# old_control_board.net
KiCad netlist of a schematic drawn in EAGLE
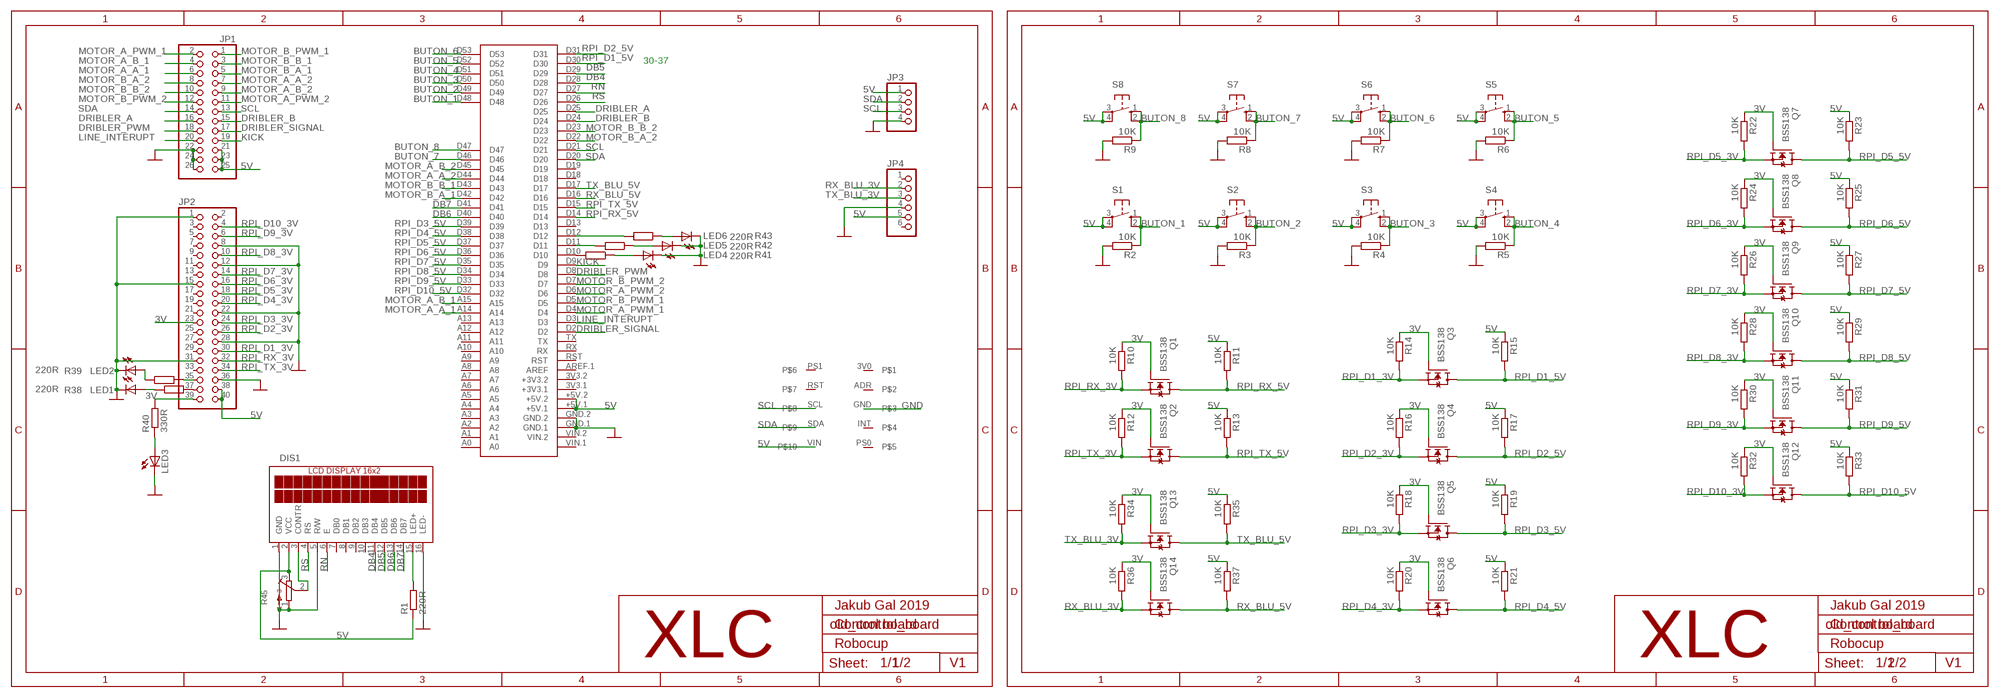
[diagram p0: schematic, sheet 1]

(export (version "E")
  (design (tool "Eeschema 10.0.6"))
  (components
    (comp (ref "DIS1")
      (value "LCD_DISPLEJ_16X2Z")
      (footprint "eagle-import:LCD_DISPLEJ_16X2")
      (libsource (lib "eagle-import") (part "LCD_DISPLEJ_16X2Z"))
    )
    (comp (ref "JP1")
      (value "PINHD-2X13_2.54")
      (footprint "eagle-import:2X13")
      (libsource (lib "eagle-import") (part "PINHD-2X13_2.54"))
    )
    (comp (ref "JP2")
      (value "PINHD-2X20_2.54")
      (footprint "eagle-import:2X20")
      (libsource (lib "eagle-import") (part "PINHD-2X20_2.54"))
    )
    (comp (ref "JP3")
      (value "PINHD-1X4_2.54")
      (footprint "eagle-import:1X04")
      (libsource (lib "eagle-import") (part "PINHD-1X4_2.54"))
    )
    (comp (ref "JP4")
      (value "PINHD-1X6_2.54")
      (footprint "eagle-import:1X06")
      (libsource (lib "eagle-import") (part "PINHD-1X6_2.54"))
    )
    (comp (ref "LED1")
      (value "LEDCHIPLED_0603")
      (footprint "eagle-import:CHIPLED_0603")
      (libsource (lib "eagle-import") (part "LEDCHIPLED_0603"))
    )
    (comp (ref "LED2")
      (value "LEDCHIPLED_0603")
      (footprint "eagle-import:CHIPLED_0603")
      (libsource (lib "eagle-import") (part "LEDCHIPLED_0603"))
    )
    (comp (ref "LED3")
      (value "LEDCHIPLED_0603")
      (footprint "eagle-import:CHIPLED_0603")
      (libsource (lib "eagle-import") (part "LEDCHIPLED_0603"))
    )
    (comp (ref "LED4")
      (value "LEDCHIPLED_0603")
      (footprint "eagle-import:CHIPLED_0603")
      (libsource (lib "eagle-import") (part "LEDCHIPLED_0603"))
    )
    (comp (ref "LED5")
      (value "LEDCHIPLED_0603")
      (footprint "eagle-import:CHIPLED_0603")
      (libsource (lib "eagle-import") (part "LEDCHIPLED_0603"))
    )
    (comp (ref "LED6")
      (value "LEDCHIPLED_0603")
      (footprint "eagle-import:CHIPLED_0603")
      (libsource (lib "eagle-import") (part "LEDCHIPLED_0603"))
    )
    (comp (ref "Q1")
      (value "BSS138")
      (footprint "eagle-import:SOT23")
      (fields (field (name "MF") "Fairchild"))
      (libsource (lib "eagle-import") (part "BSS138"))
    )
    (comp (ref "Q2")
      (value "BSS138")
      (footprint "eagle-import:SOT23")
      (fields (field (name "MF") "Fairchild"))
      (libsource (lib "eagle-import") (part "BSS138"))
    )
    (comp (ref "Q3")
      (value "BSS138")
      (footprint "eagle-import:SOT23")
      (fields (field (name "MF") "Fairchild"))
      (libsource (lib "eagle-import") (part "BSS138"))
    )
    (comp (ref "Q4")
      (value "BSS138")
      (footprint "eagle-import:SOT23")
      (fields (field (name "MF") "Fairchild"))
      (libsource (lib "eagle-import") (part "BSS138"))
    )
    (comp (ref "Q5")
      (value "BSS138")
      (footprint "eagle-import:SOT23")
      (fields (field (name "MF") "Fairchild"))
      (libsource (lib "eagle-import") (part "BSS138"))
    )
    (comp (ref "Q6")
      (value "BSS138")
      (footprint "eagle-import:SOT23")
      (fields (field (name "MF") "Fairchild"))
      (libsource (lib "eagle-import") (part "BSS138"))
    )
    (comp (ref "Q7")
      (value "BSS138")
      (footprint "eagle-import:SOT23")
      (fields (field (name "MF") "Fairchild"))
      (libsource (lib "eagle-import") (part "BSS138"))
    )
    (comp (ref "Q8")
      (value "BSS138")
      (footprint "eagle-import:SOT23")
      (fields (field (name "MF") "Fairchild"))
      (libsource (lib "eagle-import") (part "BSS138"))
    )
    (comp (ref "Q9")
      (value "BSS138")
      (footprint "eagle-import:SOT23")
      (fields (field (name "MF") "Fairchild"))
      (libsource (lib "eagle-import") (part "BSS138"))
    )
    (comp (ref "Q10")
      (value "BSS138")
      (footprint "eagle-import:SOT23")
      (fields (field (name "MF") "Fairchild"))
      (libsource (lib "eagle-import") (part "BSS138"))
    )
    (comp (ref "Q11")
      (value "BSS138")
      (footprint "eagle-import:SOT23")
      (fields (field (name "MF") "Fairchild"))
      (libsource (lib "eagle-import") (part "BSS138"))
    )
    (comp (ref "Q12")
      (value "BSS138")
      (footprint "eagle-import:SOT23")
      (fields (field (name "MF") "Fairchild"))
      (libsource (lib "eagle-import") (part "BSS138"))
    )
    (comp (ref "Q13")
      (value "BSS138")
      (footprint "eagle-import:SOT23")
      (fields (field (name "MF") "Fairchild"))
      (libsource (lib "eagle-import") (part "BSS138"))
    )
    (comp (ref "Q14")
      (value "BSS138")
      (footprint "eagle-import:SOT23")
      (fields (field (name "MF") "Fairchild"))
      (libsource (lib "eagle-import") (part "BSS138"))
    )
    (comp (ref "R1")
      (value "220R")
      (footprint "eagle-import:R0603")
      (libsource (lib "eagle-import") (part "R-EU_R0603"))
    )
    (comp (ref "R2")
      (value "10K")
      (footprint "eagle-import:R0603")
      (libsource (lib "eagle-import") (part "R-EU_R0603"))
    )
    (comp (ref "R3")
      (value "10K")
      (footprint "eagle-import:R0603")
      (libsource (lib "eagle-import") (part "R-EU_R0603"))
    )
    (comp (ref "R4")
      (value "10K")
      (footprint "eagle-import:R0603")
      (libsource (lib "eagle-import") (part "R-EU_R0603"))
    )
    (comp (ref "R5")
      (value "10K")
      (footprint "eagle-import:R0603")
      (libsource (lib "eagle-import") (part "R-EU_R0603"))
    )
    (comp (ref "R6")
      (value "10K")
      (footprint "eagle-import:R0603")
      (libsource (lib "eagle-import") (part "R-EU_R0603"))
    )
    (comp (ref "R7")
      (value "10K")
      (footprint "eagle-import:R0603")
      (libsource (lib "eagle-import") (part "R-EU_R0603"))
    )
    (comp (ref "R8")
      (value "10K")
      (footprint "eagle-import:R0603")
      (libsource (lib "eagle-import") (part "R-EU_R0603"))
    )
    (comp (ref "R9")
      (value "10K")
      (footprint "eagle-import:R0603")
      (libsource (lib "eagle-import") (part "R-EU_R0603"))
    )
    (comp (ref "R10")
      (value "10K")
      (footprint "eagle-import:R0603")
      (libsource (lib "eagle-import") (part "R-EU_R0603"))
    )
    (comp (ref "R11")
      (value "10K")
      (footprint "eagle-import:R0603")
      (libsource (lib "eagle-import") (part "R-EU_R0603"))
    )
    (comp (ref "R12")
      (value "10K")
      (footprint "eagle-import:R0603")
      (libsource (lib "eagle-import") (part "R-EU_R0603"))
    )
    (comp (ref "R13")
      (value "10K")
      (footprint "eagle-import:R0603")
      (libsource (lib "eagle-import") (part "R-EU_R0603"))
    )
    (comp (ref "R14")
      (value "10K")
      (footprint "eagle-import:R0603")
      (libsource (lib "eagle-import") (part "R-EU_R0603"))
    )
    (comp (ref "R15")
      (value "10K")
      (footprint "eagle-import:R0603")
      (libsource (lib "eagle-import") (part "R-EU_R0603"))
    )
    (comp (ref "R16")
      (value "10K")
      (footprint "eagle-import:R0603")
      (libsource (lib "eagle-import") (part "R-EU_R0603"))
    )
    (comp (ref "R17")
      (value "10K")
      (footprint "eagle-import:R0603")
      (libsource (lib "eagle-import") (part "R-EU_R0603"))
    )
    (comp (ref "R18")
      (value "10K")
      (footprint "eagle-import:R0603")
      (libsource (lib "eagle-import") (part "R-EU_R0603"))
    )
    (comp (ref "R19")
      (value "10K")
      (footprint "eagle-import:R0603")
      (libsource (lib "eagle-import") (part "R-EU_R0603"))
    )
    (comp (ref "R20")
      (value "10K")
      (footprint "eagle-import:R0603")
      (libsource (lib "eagle-import") (part "R-EU_R0603"))
    )
    (comp (ref "R21")
      (value "10K")
      (footprint "eagle-import:R0603")
      (libsource (lib "eagle-import") (part "R-EU_R0603"))
    )
    (comp (ref "R22")
      (value "10K")
      (footprint "eagle-import:R0603")
      (libsource (lib "eagle-import") (part "R-EU_R0603"))
    )
    (comp (ref "R23")
      (value "10K")
      (footprint "eagle-import:R0603")
      (libsource (lib "eagle-import") (part "R-EU_R0603"))
    )
    (comp (ref "R24")
      (value "10K")
      (footprint "eagle-import:R0603")
      (libsource (lib "eagle-import") (part "R-EU_R0603"))
    )
    (comp (ref "R25")
      (value "10K")
      (footprint "eagle-import:R0603")
      (libsource (lib "eagle-import") (part "R-EU_R0603"))
    )
    (comp (ref "R26")
      (value "10K")
      (footprint "eagle-import:R0603")
      (libsource (lib "eagle-import") (part "R-EU_R0603"))
    )
    (comp (ref "R27")
      (value "10K")
      (footprint "eagle-import:R0603")
      (libsource (lib "eagle-import") (part "R-EU_R0603"))
    )
    (comp (ref "R28")
      (value "10K")
      (footprint "eagle-import:R0603")
      (libsource (lib "eagle-import") (part "R-EU_R0603"))
    )
    (comp (ref "R29")
      (value "10K")
      (footprint "eagle-import:R0603")
      (libsource (lib "eagle-import") (part "R-EU_R0603"))
    )
    (comp (ref "R30")
      (value "10K")
      (footprint "eagle-import:R0603")
      (libsource (lib "eagle-import") (part "R-EU_R0603"))
    )
    (comp (ref "R31")
      (value "10K")
      (footprint "eagle-import:R0603")
      (libsource (lib "eagle-import") (part "R-EU_R0603"))
    )
    (comp (ref "R32")
      (value "10K")
      (footprint "eagle-import:R0603")
      (libsource (lib "eagle-import") (part "R-EU_R0603"))
    )
    (comp (ref "R33")
      (value "10K")
      (footprint "eagle-import:R0603")
      (libsource (lib "eagle-import") (part "R-EU_R0603"))
    )
    (comp (ref "R34")
      (value "10K")
      (footprint "eagle-import:R0603")
      (libsource (lib "eagle-import") (part "R-EU_R0603"))
    )
    (comp (ref "R35")
      (value "10K")
      (footprint "eagle-import:R0603")
      (libsource (lib "eagle-import") (part "R-EU_R0603"))
    )
    (comp (ref "R36")
      (value "10K")
      (footprint "eagle-import:R0603")
      (libsource (lib "eagle-import") (part "R-EU_R0603"))
    )
    (comp (ref "R37")
      (value "10K")
      (footprint "eagle-import:R0603")
      (libsource (lib "eagle-import") (part "R-EU_R0603"))
    )
    (comp (ref "R38")
      (value "220R")
      (footprint "eagle-import:R0603")
      (libsource (lib "eagle-import") (part "R-EU_R0603"))
    )
    (comp (ref "R39")
      (value "220R")
      (footprint "eagle-import:R0603")
      (libsource (lib "eagle-import") (part "R-EU_R0603"))
    )
    (comp (ref "R40")
      (value "330R")
      (footprint "eagle-import:R0603")
      (libsource (lib "eagle-import") (part "R-EU_R0603"))
    )
    (comp (ref "R41")
      (value "220R")
      (footprint "eagle-import:R0603")
      (libsource (lib "eagle-import") (part "R-EU_R0603"))
    )
    (comp (ref "R42")
      (value "220R")
      (footprint "eagle-import:R0603")
      (libsource (lib "eagle-import") (part "R-EU_R0603"))
    )
    (comp (ref "R43")
      (value "220R")
      (footprint "eagle-import:R0603")
      (libsource (lib "eagle-import") (part "R-EU_R0603"))
    )
    (comp (ref "R45")
      (value "3362P")
      (footprint "eagle-import:3362P")
      (libsource (lib "eagle-import") (part "3362P"))
    )
    (comp (ref "S1")
      (value "10-XX")
      (footprint "eagle-import:B3F-10XX")
      (fields (field (name "MPN") "B3F-1000"))
      (libsource (lib "eagle-import") (part "10-XX"))
    )
    (comp (ref "S2")
      (value "10-XX")
      (footprint "eagle-import:B3F-10XX")
      (fields (field (name "MPN") "B3F-1000"))
      (libsource (lib "eagle-import") (part "10-XX"))
    )
    (comp (ref "S3")
      (value "10-XX")
      (footprint "eagle-import:B3F-10XX")
      (fields (field (name "MPN") "B3F-1000"))
      (libsource (lib "eagle-import") (part "10-XX"))
    )
    (comp (ref "S4")
      (value "10-XX")
      (footprint "eagle-import:B3F-10XX")
      (fields (field (name "MPN") "B3F-1000"))
      (libsource (lib "eagle-import") (part "10-XX"))
    )
    (comp (ref "S5")
      (value "10-XX")
      (footprint "eagle-import:B3F-10XX")
      (fields (field (name "MPN") "B3F-1000"))
      (libsource (lib "eagle-import") (part "10-XX"))
    )
    (comp (ref "S6")
      (value "10-XX")
      (footprint "eagle-import:B3F-10XX")
      (fields (field (name "MPN") "B3F-1000"))
      (libsource (lib "eagle-import") (part "10-XX"))
    )
    (comp (ref "S7")
      (value "10-XX")
      (footprint "eagle-import:B3F-10XX")
      (fields (field (name "MPN") "B3F-1000"))
      (libsource (lib "eagle-import") (part "10-XX"))
    )
    (comp (ref "S8")
      (value "10-XX")
      (footprint "eagle-import:B3F-10XX")
      (fields (field (name "MPN") "B3F-1000"))
      (libsource (lib "eagle-import") (part "10-XX"))
    )
    (comp (ref "U$1")
      (value "MEGA2560_MIKRO")
      (footprint "eagle-import:MEGA2560_MIKRO")
      (libsource (lib "eagle-import") (part "MEGA2560_MIKRO"))
    )
    (comp (ref "U$2")
      (value "BNO055")
      (footprint "eagle-import:BNO005")
      (libsource (lib "eagle-import") (part "BNO055"))
    )
  )
  (nets
    (net (code "1") (name "/3V") (class "Default")
      (node (ref "JP2") (pin "23") (pinfunction "23_23") (pintype "passive"))
      (node (ref "JP2") (pin "39") (pinfunction "39_39") (pintype "passive"))
      (node (ref "Q1") (pin "1") (pinfunction "G_1") (pintype "passive"))
      (node (ref "Q10") (pin "1") (pinfunction "G_1") (pintype "passive"))
      (node (ref "Q11") (pin "1") (pinfunction "G_1") (pintype "passive"))
      (node (ref "Q12") (pin "1") (pinfunction "G_1") (pintype "passive"))
      (node (ref "Q13") (pin "1") (pinfunction "G_1") (pintype "passive"))
      (node (ref "Q14") (pin "1") (pinfunction "G_1") (pintype "passive"))
      (node (ref "Q2") (pin "1") (pinfunction "G_1") (pintype "passive"))
      (node (ref "Q3") (pin "1") (pinfunction "G_1") (pintype "passive"))
      (node (ref "Q4") (pin "1") (pinfunction "G_1") (pintype "passive"))
      (node (ref "Q5") (pin "1") (pinfunction "G_1") (pintype "passive"))
      (node (ref "Q6") (pin "1") (pinfunction "G_1") (pintype "passive"))
      (node (ref "Q7") (pin "1") (pinfunction "G_1") (pintype "passive"))
      (node (ref "Q8") (pin "1") (pinfunction "G_1") (pintype "passive"))
      (node (ref "Q9") (pin "1") (pinfunction "G_1") (pintype "passive"))
      (node (ref "R10") (pin "1") (pinfunction "1_1") (pintype "passive"))
      (node (ref "R12") (pin "1") (pinfunction "1_1") (pintype "passive"))
      (node (ref "R14") (pin "1") (pinfunction "1_1") (pintype "passive"))
      (node (ref "R16") (pin "1") (pinfunction "1_1") (pintype "passive"))
      (node (ref "R18") (pin "1") (pinfunction "1_1") (pintype "passive"))
      (node (ref "R20") (pin "1") (pinfunction "1_1") (pintype "passive"))
      (node (ref "R22") (pin "1") (pinfunction "1_1") (pintype "passive"))
      (node (ref "R24") (pin "1") (pinfunction "1_1") (pintype "passive"))
      (node (ref "R26") (pin "1") (pinfunction "1_1") (pintype "passive"))
      (node (ref "R28") (pin "1") (pinfunction "1_1") (pintype "passive"))
      (node (ref "R30") (pin "1") (pinfunction "1_1") (pintype "passive"))
      (node (ref "R32") (pin "1") (pinfunction "1_1") (pintype "passive"))
      (node (ref "R34") (pin "1") (pinfunction "1_1") (pintype "passive"))
      (node (ref "R36") (pin "1") (pinfunction "1_1") (pintype "passive"))
      (node (ref "R40") (pin "2") (pinfunction "2_2") (pintype "passive"))
    )
    (net (code "2") (name "/5V") (class "Default")
      (node (ref "DIS1") (pin "2") (pinfunction "VCC_2") (pintype "power_in"))
      (node (ref "JP1") (pin "21") (pinfunction "21_21") (pintype "passive"))
      (node (ref "JP1") (pin "23") (pinfunction "23_23") (pintype "passive"))
      (node (ref "JP1") (pin "25") (pinfunction "25_25") (pintype "passive"))
      (node (ref "JP2") (pin "38") (pinfunction "38_38") (pintype "passive"))
      (node (ref "JP2") (pin "40") (pinfunction "40_40") (pintype "passive"))
      (node (ref "JP3") (pin "1") (pinfunction "1_1") (pintype "passive"))
      (node (ref "JP4") (pin "5") (pinfunction "5_5") (pintype "passive"))
      (node (ref "R1") (pin "1") (pinfunction "1_1") (pintype "passive"))
      (node (ref "R11") (pin "1") (pinfunction "1_1") (pintype "passive"))
      (node (ref "R13") (pin "1") (pinfunction "1_1") (pintype "passive"))
      (node (ref "R15") (pin "1") (pinfunction "1_1") (pintype "passive"))
      (node (ref "R17") (pin "1") (pinfunction "1_1") (pintype "passive"))
      (node (ref "R19") (pin "1") (pinfunction "1_1") (pintype "passive"))
      (node (ref "R21") (pin "1") (pinfunction "1_1") (pintype "passive"))
      (node (ref "R23") (pin "1") (pinfunction "1_1") (pintype "passive"))
      (node (ref "R25") (pin "1") (pinfunction "1_1") (pintype "passive"))
      (node (ref "R27") (pin "1") (pinfunction "1_1") (pintype "passive"))
      (node (ref "R29") (pin "1") (pinfunction "1_1") (pintype "passive"))
      (node (ref "R31") (pin "1") (pinfunction "1_1") (pintype "passive"))
      (node (ref "R33") (pin "1") (pinfunction "1_1") (pintype "passive"))
      (node (ref "R35") (pin "1") (pinfunction "1_1") (pintype "passive"))
      (node (ref "R37") (pin "1") (pinfunction "1_1") (pintype "passive"))
      (node (ref "R45") (pin "3") (pinfunction "3_3") (pintype "passive"))
      (node (ref "S1") (pin "3") (pinfunction "P_3") (pintype "passive"))
      (node (ref "S1") (pin "4") (pinfunction "P1_4") (pintype "passive"))
      (node (ref "S2") (pin "3") (pinfunction "P_3") (pintype "passive"))
      (node (ref "S2") (pin "4") (pinfunction "P1_4") (pintype "passive"))
      (node (ref "S3") (pin "3") (pinfunction "P_3") (pintype "passive"))
      (node (ref "S3") (pin "4") (pinfunction "P1_4") (pintype "passive"))
      (node (ref "S4") (pin "3") (pinfunction "P_3") (pintype "passive"))
      (node (ref "S4") (pin "4") (pinfunction "P1_4") (pintype "passive"))
      (node (ref "S5") (pin "3") (pinfunction "P_3") (pintype "passive"))
      (node (ref "S5") (pin "4") (pinfunction "P1_4") (pintype "passive"))
      (node (ref "S6") (pin "3") (pinfunction "P_3") (pintype "passive"))
      (node (ref "S6") (pin "4") (pinfunction "P1_4") (pintype "passive"))
      (node (ref "S7") (pin "3") (pinfunction "P_3") (pintype "passive"))
      (node (ref "S7") (pin "4") (pinfunction "P1_4") (pintype "passive"))
      (node (ref "S8") (pin "3") (pinfunction "P_3") (pintype "passive"))
      (node (ref "S8") (pin "4") (pinfunction "P1_4") (pintype "passive"))
      (node (ref "U$1") (pin "+5V.1") (pinfunction "+5V.1_+5V.1") (pintype "bidirectional"))
      (node (ref "U$1") (pin "+5V.2") (pinfunction "+5V.2_+5V.2") (pintype "bidirectional"))
      (node (ref "U$2") (pin "VIN") (pinfunction "P$10_VIN") (pintype "bidirectional"))
    )
    (net (code "3") (name "/BUTON_1") (class "Default")
      (node (ref "R2") (pin "1") (pinfunction "1_1") (pintype "passive"))
      (node (ref "S1") (pin "1") (pinfunction "S_1") (pintype "passive"))
      (node (ref "S1") (pin "2") (pinfunction "S1_2") (pintype "passive"))
      (node (ref "U$1") (pin "D48") (pinfunction "D48_D48") (pintype "bidirectional"))
    )
    (net (code "4") (name "/BUTON_2") (class "Default")
      (node (ref "R3") (pin "1") (pinfunction "1_1") (pintype "passive"))
      (node (ref "S2") (pin "1") (pinfunction "S_1") (pintype "passive"))
      (node (ref "S2") (pin "2") (pinfunction "S1_2") (pintype "passive"))
      (node (ref "U$1") (pin "D49") (pinfunction "D49_D49") (pintype "bidirectional"))
    )
    (net (code "5") (name "/BUTON_3") (class "Default")
      (node (ref "R4") (pin "1") (pinfunction "1_1") (pintype "passive"))
      (node (ref "S3") (pin "1") (pinfunction "S_1") (pintype "passive"))
      (node (ref "S3") (pin "2") (pinfunction "S1_2") (pintype "passive"))
      (node (ref "U$1") (pin "D50") (pinfunction "D50_D50") (pintype "bidirectional"))
    )
    (net (code "6") (name "/BUTON_4") (class "Default")
      (node (ref "R5") (pin "1") (pinfunction "1_1") (pintype "passive"))
      (node (ref "S4") (pin "1") (pinfunction "S_1") (pintype "passive"))
      (node (ref "S4") (pin "2") (pinfunction "S1_2") (pintype "passive"))
      (node (ref "U$1") (pin "D51") (pinfunction "D51_D51") (pintype "bidirectional"))
    )
    (net (code "7") (name "/BUTON_5") (class "Default")
      (node (ref "R6") (pin "1") (pinfunction "1_1") (pintype "passive"))
      (node (ref "S5") (pin "1") (pinfunction "S_1") (pintype "passive"))
      (node (ref "S5") (pin "2") (pinfunction "S1_2") (pintype "passive"))
      (node (ref "U$1") (pin "D52") (pinfunction "D52_D52") (pintype "bidirectional"))
    )
    (net (code "8") (name "/BUTON_6") (class "Default")
      (node (ref "R7") (pin "1") (pinfunction "1_1") (pintype "passive"))
      (node (ref "S6") (pin "1") (pinfunction "S_1") (pintype "passive"))
      (node (ref "S6") (pin "2") (pinfunction "S1_2") (pintype "passive"))
      (node (ref "U$1") (pin "D53") (pinfunction "D53_D53") (pintype "bidirectional"))
    )
    (net (code "9") (name "/BUTON_7") (class "Default")
      (node (ref "R8") (pin "1") (pinfunction "1_1") (pintype "passive"))
      (node (ref "S7") (pin "1") (pinfunction "S_1") (pintype "passive"))
      (node (ref "S7") (pin "2") (pinfunction "S1_2") (pintype "passive"))
      (node (ref "U$1") (pin "D46") (pinfunction "D46_D46") (pintype "bidirectional"))
    )
    (net (code "10") (name "/BUTON_8") (class "Default")
      (node (ref "R9") (pin "1") (pinfunction "1_1") (pintype "passive"))
      (node (ref "S8") (pin "1") (pinfunction "S_1") (pintype "passive"))
      (node (ref "S8") (pin "2") (pinfunction "S1_2") (pintype "passive"))
      (node (ref "U$1") (pin "D47") (pinfunction "D47_D47") (pintype "bidirectional"))
    )
    (net (code "11") (name "/DB4") (class "Default")
      (node (ref "DIS1") (pin "11") (pinfunction "DB4_11") (pintype "bidirectional"))
      (node (ref "U$1") (pin "D28") (pinfunction "D28_D28") (pintype "bidirectional"))
    )
    (net (code "12") (name "/DB5") (class "Default")
      (node (ref "DIS1") (pin "12") (pinfunction "DB5_12") (pintype "bidirectional"))
      (node (ref "U$1") (pin "D29") (pinfunction "D29_D29") (pintype "bidirectional"))
    )
    (net (code "13") (name "/DB6") (class "Default")
      (node (ref "DIS1") (pin "13") (pinfunction "DB6_13") (pintype "bidirectional"))
      (node (ref "U$1") (pin "D40") (pinfunction "D40_D40") (pintype "bidirectional"))
    )
    (net (code "14") (name "/DB7") (class "Default")
      (node (ref "DIS1") (pin "14") (pinfunction "DB7_14") (pintype "bidirectional"))
      (node (ref "U$1") (pin "D41") (pinfunction "D41_D41") (pintype "bidirectional"))
    )
    (net (code "15") (name "/DRIBLER_A") (class "Default")
      (node (ref "JP1") (pin "16") (pinfunction "16_16") (pintype "passive"))
      (node (ref "U$1") (pin "D25") (pinfunction "D25_D25") (pintype "bidirectional"))
    )
    (net (code "16") (name "/DRIBLER_B") (class "Default")
      (node (ref "JP1") (pin "15") (pinfunction "15_15") (pintype "passive"))
      (node (ref "U$1") (pin "D24") (pinfunction "D24_D24") (pintype "bidirectional"))
    )
    (net (code "17") (name "/DRIBLER_PWM") (class "Default")
      (node (ref "JP1") (pin "18") (pinfunction "18_18") (pintype "passive"))
      (node (ref "U$1") (pin "D8") (pinfunction "D8_D8") (pintype "bidirectional"))
    )
    (net (code "18") (name "/DRIBLER_SIGNAL") (class "Default")
      (node (ref "JP1") (pin "17") (pinfunction "17_17") (pintype "passive"))
      (node (ref "U$1") (pin "D2") (pinfunction "D2_D2") (pintype "bidirectional"))
    )
    (net (code "19") (name "/KICK") (class "Default")
      (node (ref "JP1") (pin "19") (pinfunction "19_19") (pintype "passive"))
      (node (ref "U$1") (pin "D9") (pinfunction "D9_D9") (pintype "bidirectional"))
    )
    (net (code "20") (name "/LINE_INTERUPT") (class "Default")
      (node (ref "JP1") (pin "20") (pinfunction "20_20") (pintype "passive"))
      (node (ref "U$1") (pin "D3") (pinfunction "D3_D3") (pintype "bidirectional"))
    )
    (net (code "21") (name "/MOTOR_A_A_1") (class "Default")
      (node (ref "JP1") (pin "6") (pinfunction "6_6") (pintype "passive"))
      (node (ref "U$1") (pin "A14") (pinfunction "A14_A14") (pintype "bidirectional"))
    )
    (net (code "22") (name "/MOTOR_A_A_2") (class "Default")
      (node (ref "JP1") (pin "7") (pinfunction "7_7") (pintype "passive"))
      (node (ref "U$1") (pin "D44") (pinfunction "D44_D44") (pintype "bidirectional"))
    )
    (net (code "23") (name "/MOTOR_A_B_1") (class "Default")
      (node (ref "JP1") (pin "4") (pinfunction "4_4") (pintype "passive"))
      (node (ref "U$1") (pin "A15") (pinfunction "A15_A15") (pintype "bidirectional"))
    )
    (net (code "24") (name "/MOTOR_A_B_2") (class "Default")
      (node (ref "JP1") (pin "9") (pinfunction "9_9") (pintype "passive"))
      (node (ref "U$1") (pin "D45") (pinfunction "D45_D45") (pintype "bidirectional"))
    )
    (net (code "25") (name "/MOTOR_A_PWM_1") (class "Default")
      (node (ref "JP1") (pin "2") (pinfunction "2_2") (pintype "passive"))
      (node (ref "U$1") (pin "D4") (pinfunction "D4_D4") (pintype "bidirectional"))
    )
    (net (code "26") (name "/MOTOR_A_PWM_2") (class "Default")
      (node (ref "JP1") (pin "11") (pinfunction "11_11") (pintype "passive"))
      (node (ref "U$1") (pin "D6") (pinfunction "D6_D6") (pintype "bidirectional"))
    )
    (net (code "27") (name "/MOTOR_B_A_1") (class "Default")
      (node (ref "JP1") (pin "5") (pinfunction "5_5") (pintype "passive"))
      (node (ref "U$1") (pin "D42") (pinfunction "D42_D42") (pintype "bidirectional"))
    )
    (net (code "28") (name "/MOTOR_B_A_2") (class "Default")
      (node (ref "JP1") (pin "8") (pinfunction "8_8") (pintype "passive"))
      (node (ref "U$1") (pin "D22") (pinfunction "D22_D22") (pintype "bidirectional"))
    )
    (net (code "29") (name "/MOTOR_B_B_1") (class "Default")
      (node (ref "JP1") (pin "3") (pinfunction "3_3") (pintype "passive"))
      (node (ref "U$1") (pin "D43") (pinfunction "D43_D43") (pintype "bidirectional"))
    )
    (net (code "30") (name "/MOTOR_B_B_2") (class "Default")
      (node (ref "JP1") (pin "10") (pinfunction "10_10") (pintype "passive"))
      (node (ref "U$1") (pin "D23") (pinfunction "D23_D23") (pintype "bidirectional"))
    )
    (net (code "31") (name "/MOTOR_B_PWM_1") (class "Default")
      (node (ref "JP1") (pin "1") (pinfunction "1_1") (pintype "passive"))
      (node (ref "U$1") (pin "D5") (pinfunction "D5_D5") (pintype "bidirectional"))
    )
    (net (code "32") (name "/MOTOR_B_PWM_2") (class "Default")
      (node (ref "JP1") (pin "12") (pinfunction "12_12") (pintype "passive"))
      (node (ref "U$1") (pin "D7") (pinfunction "D7_D7") (pintype "bidirectional"))
    )
    (net (code "33") (name "/RN") (class "Default")
      (node (ref "DIS1") (pin "6") (pinfunction "E_6") (pintype "input"))
      (node (ref "U$1") (pin "D27") (pinfunction "D27_D27") (pintype "bidirectional"))
    )
    (net (code "34") (name "/RPI_D1_3V") (class "Default")
      (node (ref "JP2") (pin "30") (pinfunction "30_30") (pintype "passive"))
      (node (ref "Q3") (pin "2") (pinfunction "S_2") (pintype "passive"))
      (node (ref "R14") (pin "2") (pinfunction "2_2") (pintype "passive"))
    )
    (net (code "35") (name "/RPI_D1_5V") (class "Default")
      (node (ref "Q3") (pin "3") (pinfunction "D_3") (pintype "passive"))
      (node (ref "R15") (pin "2") (pinfunction "2_2") (pintype "passive"))
      (node (ref "U$1") (pin "D30") (pinfunction "D30_D30") (pintype "bidirectional"))
    )
    (net (code "36") (name "/RPI_D2_3V") (class "Default")
      (node (ref "JP2") (pin "26") (pinfunction "26_26") (pintype "passive"))
      (node (ref "Q4") (pin "2") (pinfunction "S_2") (pintype "passive"))
      (node (ref "R16") (pin "2") (pinfunction "2_2") (pintype "passive"))
    )
    (net (code "37") (name "/RPI_D2_5V") (class "Default")
      (node (ref "Q4") (pin "3") (pinfunction "D_3") (pintype "passive"))
      (node (ref "R17") (pin "2") (pinfunction "2_2") (pintype "passive"))
      (node (ref "U$1") (pin "D31") (pinfunction "D31_D31") (pintype "bidirectional"))
    )
    (net (code "38") (name "/RPI_D3_3V") (class "Default")
      (node (ref "JP2") (pin "24") (pinfunction "24_24") (pintype "passive"))
      (node (ref "Q5") (pin "2") (pinfunction "S_2") (pintype "passive"))
      (node (ref "R18") (pin "2") (pinfunction "2_2") (pintype "passive"))
    )
    (net (code "39") (name "/RPI_D3_5V") (class "Default")
      (node (ref "Q5") (pin "3") (pinfunction "D_3") (pintype "passive"))
      (node (ref "R19") (pin "2") (pinfunction "2_2") (pintype "passive"))
      (node (ref "U$1") (pin "D39") (pinfunction "D39_D39") (pintype "bidirectional"))
    )
    (net (code "40") (name "/RPI_D4_3V") (class "Default")
      (node (ref "JP2") (pin "20") (pinfunction "20_20") (pintype "passive"))
      (node (ref "Q6") (pin "2") (pinfunction "S_2") (pintype "passive"))
      (node (ref "R20") (pin "2") (pinfunction "2_2") (pintype "passive"))
    )
    (net (code "41") (name "/RPI_D4_5V") (class "Default")
      (node (ref "Q6") (pin "3") (pinfunction "D_3") (pintype "passive"))
      (node (ref "R21") (pin "2") (pinfunction "2_2") (pintype "passive"))
      (node (ref "U$1") (pin "D38") (pinfunction "D38_D38") (pintype "bidirectional"))
    )
    (net (code "42") (name "/RPI_D5_3V") (class "Default")
      (node (ref "JP2") (pin "18") (pinfunction "18_18") (pintype "passive"))
      (node (ref "Q7") (pin "2") (pinfunction "S_2") (pintype "passive"))
      (node (ref "R22") (pin "2") (pinfunction "2_2") (pintype "passive"))
    )
    (net (code "43") (name "/RPI_D5_5V") (class "Default")
      (node (ref "Q7") (pin "3") (pinfunction "D_3") (pintype "passive"))
      (node (ref "R23") (pin "2") (pinfunction "2_2") (pintype "passive"))
      (node (ref "U$1") (pin "D37") (pinfunction "D37_D37") (pintype "bidirectional"))
    )
    (net (code "44") (name "/RPI_D6_3V") (class "Default")
      (node (ref "JP2") (pin "16") (pinfunction "16_16") (pintype "passive"))
      (node (ref "Q8") (pin "2") (pinfunction "S_2") (pintype "passive"))
      (node (ref "R24") (pin "2") (pinfunction "2_2") (pintype "passive"))
    )
    (net (code "45") (name "/RPI_D6_5V") (class "Default")
      (node (ref "Q8") (pin "3") (pinfunction "D_3") (pintype "passive"))
      (node (ref "R25") (pin "2") (pinfunction "2_2") (pintype "passive"))
      (node (ref "U$1") (pin "D36") (pinfunction "D36_D36") (pintype "bidirectional"))
    )
    (net (code "46") (name "/RPI_D7_3V") (class "Default")
      (node (ref "JP2") (pin "14") (pinfunction "14_14") (pintype "passive"))
      (node (ref "Q9") (pin "2") (pinfunction "S_2") (pintype "passive"))
      (node (ref "R26") (pin "2") (pinfunction "2_2") (pintype "passive"))
    )
    (net (code "47") (name "/RPI_D7_5V") (class "Default")
      (node (ref "Q9") (pin "3") (pinfunction "D_3") (pintype "passive"))
      (node (ref "R27") (pin "2") (pinfunction "2_2") (pintype "passive"))
      (node (ref "U$1") (pin "D35") (pinfunction "D35_D35") (pintype "bidirectional"))
    )
    (net (code "48") (name "/RPI_D8_3V") (class "Default")
      (node (ref "JP2") (pin "10") (pinfunction "10_10") (pintype "passive"))
      (node (ref "Q10") (pin "2") (pinfunction "S_2") (pintype "passive"))
      (node (ref "R28") (pin "2") (pinfunction "2_2") (pintype "passive"))
    )
    (net (code "49") (name "/RPI_D8_5V") (class "Default")
      (node (ref "Q10") (pin "3") (pinfunction "D_3") (pintype "passive"))
      (node (ref "R29") (pin "2") (pinfunction "2_2") (pintype "passive"))
      (node (ref "U$1") (pin "D34") (pinfunction "D34_D34") (pintype "bidirectional"))
    )
    (net (code "50") (name "/RPI_D9_3V") (class "Default")
      (node (ref "JP2") (pin "6") (pinfunction "6_6") (pintype "passive"))
      (node (ref "Q11") (pin "2") (pinfunction "S_2") (pintype "passive"))
      (node (ref "R30") (pin "2") (pinfunction "2_2") (pintype "passive"))
    )
    (net (code "51") (name "/RPI_D9_5V") (class "Default")
      (node (ref "Q11") (pin "3") (pinfunction "D_3") (pintype "passive"))
      (node (ref "R31") (pin "2") (pinfunction "2_2") (pintype "passive"))
      (node (ref "U$1") (pin "D33") (pinfunction "D33_D33") (pintype "bidirectional"))
    )
    (net (code "52") (name "/RPI_D10_3V") (class "Default")
      (node (ref "JP2") (pin "4") (pinfunction "4_4") (pintype "passive"))
      (node (ref "Q12") (pin "2") (pinfunction "S_2") (pintype "passive"))
      (node (ref "R32") (pin "2") (pinfunction "2_2") (pintype "passive"))
    )
    (net (code "53") (name "/RPI_D10_5V") (class "Default")
      (node (ref "Q12") (pin "3") (pinfunction "D_3") (pintype "passive"))
      (node (ref "R33") (pin "2") (pinfunction "2_2") (pintype "passive"))
      (node (ref "U$1") (pin "D32") (pinfunction "D32_D32") (pintype "bidirectional"))
    )
    (net (code "54") (name "/RPI_RX_3V") (class "Default")
      (node (ref "JP2") (pin "32") (pinfunction "32_32") (pintype "passive"))
      (node (ref "Q1") (pin "2") (pinfunction "S_2") (pintype "passive"))
      (node (ref "R10") (pin "2") (pinfunction "2_2") (pintype "passive"))
    )
    (net (code "55") (name "/RPI_RX_5V") (class "Default")
      (node (ref "Q1") (pin "3") (pinfunction "D_3") (pintype "passive"))
      (node (ref "R11") (pin "2") (pinfunction "2_2") (pintype "passive"))
      (node (ref "U$1") (pin "D14") (pinfunction "D14_D14") (pintype "bidirectional"))
    )
    (net (code "56") (name "/RPI_TX_3V") (class "Default")
      (node (ref "JP2") (pin "34") (pinfunction "34_34") (pintype "passive"))
      (node (ref "Q2") (pin "2") (pinfunction "S_2") (pintype "passive"))
      (node (ref "R12") (pin "2") (pinfunction "2_2") (pintype "passive"))
    )
    (net (code "57") (name "/RPI_TX_5V") (class "Default")
      (node (ref "Q2") (pin "3") (pinfunction "D_3") (pintype "passive"))
      (node (ref "R13") (pin "2") (pinfunction "2_2") (pintype "passive"))
      (node (ref "U$1") (pin "D15") (pinfunction "D15_D15") (pintype "bidirectional"))
    )
    (net (code "58") (name "/RS") (class "Default")
      (node (ref "DIS1") (pin "4") (pinfunction "RS_4") (pintype "input"))
      (node (ref "U$1") (pin "D26") (pinfunction "D26_D26") (pintype "bidirectional"))
    )
    (net (code "59") (name "/RX_BLU_3V") (class "Default")
      (node (ref "JP4") (pin "2") (pinfunction "2_2") (pintype "passive"))
      (node (ref "Q14") (pin "2") (pinfunction "S_2") (pintype "passive"))
      (node (ref "R36") (pin "2") (pinfunction "2_2") (pintype "passive"))
    )
    (net (code "60") (name "/RX_BLU_5V") (class "Default")
      (node (ref "Q14") (pin "3") (pinfunction "D_3") (pintype "passive"))
      (node (ref "R37") (pin "2") (pinfunction "2_2") (pintype "passive"))
      (node (ref "U$1") (pin "D16") (pinfunction "D16_D16") (pintype "bidirectional"))
    )
    (net (code "61") (name "/SCL") (class "Default")
      (node (ref "JP1") (pin "13") (pinfunction "13_13") (pintype "passive"))
      (node (ref "JP3") (pin "3") (pinfunction "3_3") (pintype "passive"))
      (node (ref "U$1") (pin "D21") (pinfunction "D21_D21") (pintype "bidirectional"))
      (node (ref "U$2") (pin "SCL") (pinfunction "P$8_SCL") (pintype "bidirectional"))
    )
    (net (code "62") (name "/SDA") (class "Default")
      (node (ref "JP1") (pin "14") (pinfunction "14_14") (pintype "passive"))
      (node (ref "JP3") (pin "2") (pinfunction "2_2") (pintype "passive"))
      (node (ref "U$1") (pin "D20") (pinfunction "D20_D20") (pintype "bidirectional"))
      (node (ref "U$2") (pin "SDA") (pinfunction "P$9_SDA") (pintype "bidirectional"))
    )
    (net (code "63") (name "/TX_BLU_3V") (class "Default")
      (node (ref "JP4") (pin "3") (pinfunction "3_3") (pintype "passive"))
      (node (ref "Q13") (pin "2") (pinfunction "S_2") (pintype "passive"))
      (node (ref "R34") (pin "2") (pinfunction "2_2") (pintype "passive"))
    )
    (net (code "64") (name "/TX_BLU_5V") (class "Default")
      (node (ref "Q13") (pin "3") (pinfunction "D_3") (pintype "passive"))
      (node (ref "R35") (pin "2") (pinfunction "2_2") (pintype "passive"))
      (node (ref "U$1") (pin "D17") (pinfunction "D17_D17") (pintype "bidirectional"))
    )
    (net (code "65") (name "GND") (class "Default")
      (node (ref "DIS1") (pin "1") (pinfunction "GND_1") (pintype "power_in"))
      (node (ref "DIS1") (pin "16") (pinfunction "LED-_16") (pintype "passive"))
      (node (ref "DIS1") (pin "5") (pinfunction "R/W_5") (pintype "input"))
      (node (ref "JP1") (pin "22") (pinfunction "22_22") (pintype "passive"))
      (node (ref "JP1") (pin "24") (pinfunction "24_24") (pintype "passive"))
      (node (ref "JP1") (pin "26") (pinfunction "26_26") (pintype "passive"))
      (node (ref "JP2") (pin "1") (pinfunction "1_1") (pintype "passive"))
      (node (ref "JP2") (pin "12") (pinfunction "12_12") (pintype "passive"))
      (node (ref "JP2") (pin "15") (pinfunction "15_15") (pintype "passive"))
      (node (ref "JP2") (pin "22") (pinfunction "22_22") (pintype "passive"))
      (node (ref "JP2") (pin "28") (pinfunction "28_28") (pintype "passive"))
      (node (ref "JP2") (pin "31") (pinfunction "31_31") (pintype "passive"))
      (node (ref "JP2") (pin "36") (pinfunction "36_36") (pintype "passive"))
      (node (ref "JP2") (pin "8") (pinfunction "8_8") (pintype "passive"))
      (node (ref "JP3") (pin "4") (pinfunction "4_4") (pintype "passive"))
      (node (ref "JP4") (pin "4") (pinfunction "4_4") (pintype "passive"))
      (node (ref "LED1") (pin "C") (pinfunction "C_C") (pintype "passive"))
      (node (ref "LED2") (pin "C") (pinfunction "C_C") (pintype "passive"))
      (node (ref "LED3") (pin "C") (pinfunction "C_C") (pintype "passive"))
      (node (ref "LED4") (pin "C") (pinfunction "C_C") (pintype "passive"))
      (node (ref "LED5") (pin "C") (pinfunction "C_C") (pintype "passive"))
      (node (ref "LED6") (pin "C") (pinfunction "C_C") (pintype "passive"))
      (node (ref "R2") (pin "2") (pinfunction "2_2") (pintype "passive"))
      (node (ref "R3") (pin "2") (pinfunction "2_2") (pintype "passive"))
      (node (ref "R4") (pin "2") (pinfunction "2_2") (pintype "passive"))
      (node (ref "R45") (pin "1") (pinfunction "1_1") (pintype "passive"))
      (node (ref "R5") (pin "2") (pinfunction "2_2") (pintype "passive"))
      (node (ref "R6") (pin "2") (pinfunction "2_2") (pintype "passive"))
      (node (ref "R7") (pin "2") (pinfunction "2_2") (pintype "passive"))
      (node (ref "R8") (pin "2") (pinfunction "2_2") (pintype "passive"))
      (node (ref "R9") (pin "2") (pinfunction "2_2") (pintype "passive"))
      (node (ref "U$1") (pin "GND.1") (pinfunction "GND.1_GND.1") (pintype "bidirectional"))
      (node (ref "U$1") (pin "GND.2") (pinfunction "GND.2_GND.2") (pintype "bidirectional"))
      (node (ref "U$2") (pin "GND") (pinfunction "P$3_GND") (pintype "bidirectional"))
    )
    (net (code "66") (name "Net-(DIS1-CONTR)") (class "Default")
      (node (ref "DIS1") (pin "3") (pinfunction "CONTR_3") (pintype "input"))
      (node (ref "R45") (pin "2") (pinfunction "2_2") (pintype "passive"))
    )
    (net (code "67") (name "Net-(DIS1-LED+)") (class "Default")
      (node (ref "DIS1") (pin "15") (pinfunction "LED+_15") (pintype "passive"))
      (node (ref "R1") (pin "2") (pinfunction "2_2") (pintype "passive"))
    )
    (net (code "68") (name "Net-(JP2-Pad35)") (class "Default")
      (node (ref "JP2") (pin "35") (pinfunction "35_35") (pintype "passive"))
      (node (ref "R39") (pin "2") (pinfunction "2_2") (pintype "passive"))
    )
    (net (code "69") (name "Net-(JP2-Pad37)") (class "Default")
      (node (ref "JP2") (pin "37") (pinfunction "37_37") (pintype "passive"))
      (node (ref "R38") (pin "2") (pinfunction "2_2") (pintype "passive"))
    )
    (net (code "70") (name "Net-(LED1-PadA)") (class "Default")
      (node (ref "LED1") (pin "A") (pinfunction "A_A") (pintype "passive"))
      (node (ref "R38") (pin "1") (pinfunction "1_1") (pintype "passive"))
    )
    (net (code "71") (name "Net-(LED2-PadA)") (class "Default")
      (node (ref "LED2") (pin "A") (pinfunction "A_A") (pintype "passive"))
      (node (ref "R39") (pin "1") (pinfunction "1_1") (pintype "passive"))
    )
    (net (code "72") (name "Net-(LED3-PadA)") (class "Default")
      (node (ref "LED3") (pin "A") (pinfunction "A_A") (pintype "passive"))
      (node (ref "R40") (pin "1") (pinfunction "1_1") (pintype "passive"))
    )
    (net (code "73") (name "Net-(LED4-PadA)") (class "Default")
      (node (ref "LED4") (pin "A") (pinfunction "A_A") (pintype "passive"))
      (node (ref "R41") (pin "1") (pinfunction "1_1") (pintype "passive"))
    )
    (net (code "74") (name "Net-(LED5-PadA)") (class "Default")
      (node (ref "LED5") (pin "A") (pinfunction "A_A") (pintype "passive"))
      (node (ref "R42") (pin "1") (pinfunction "1_1") (pintype "passive"))
    )
    (net (code "75") (name "Net-(LED6-PadA)") (class "Default")
      (node (ref "LED6") (pin "A") (pinfunction "A_A") (pintype "passive"))
      (node (ref "R43") (pin "1") (pinfunction "1_1") (pintype "passive"))
    )
    (net (code "76") (name "Net-(R41-Pad2)") (class "Default")
      (node (ref "R41") (pin "2") (pinfunction "2_2") (pintype "passive"))
      (node (ref "U$1") (pin "D10") (pinfunction "D10_D10") (pintype "bidirectional"))
    )
    (net (code "77") (name "Net-(R42-Pad2)") (class "Default")
      (node (ref "R42") (pin "2") (pinfunction "2_2") (pintype "passive"))
      (node (ref "U$1") (pin "D11") (pinfunction "D11_D11") (pintype "bidirectional"))
    )
    (net (code "78") (name "Net-(R43-Pad2)") (class "Default")
      (node (ref "R43") (pin "2") (pinfunction "2_2") (pintype "passive"))
      (node (ref "U$1") (pin "D12") (pinfunction "D12_D12") (pintype "bidirectional"))
    )
    (net (code "79") (name "unconnected-(DIS1-DB0-Pad7)") (class "Default")
      (node (ref "DIS1") (pin "7") (pinfunction "DB0_7") (pintype "bidirectional"))
    )
    (net (code "80") (name "unconnected-(DIS1-DB1-Pad8)") (class "Default")
      (node (ref "DIS1") (pin "8") (pinfunction "DB1_8") (pintype "bidirectional"))
    )
    (net (code "81") (name "unconnected-(DIS1-DB2-Pad9)") (class "Default")
      (node (ref "DIS1") (pin "9") (pinfunction "DB2_9") (pintype "bidirectional"))
    )
    (net (code "82") (name "unconnected-(DIS1-DB3-Pad10)") (class "Default")
      (node (ref "DIS1") (pin "10") (pinfunction "DB3_10") (pintype "bidirectional"))
    )
    (net (code "83") (name "unconnected-(JP2-Pad2)") (class "Default")
      (node (ref "JP2") (pin "2") (pinfunction "2_2") (pintype "passive"))
    )
    (net (code "84") (name "unconnected-(JP2-Pad3)") (class "Default")
      (node (ref "JP2") (pin "3") (pinfunction "3_3") (pintype "passive"))
    )
    (net (code "85") (name "unconnected-(JP2-Pad5)") (class "Default")
      (node (ref "JP2") (pin "5") (pinfunction "5_5") (pintype "passive"))
    )
    (net (code "86") (name "unconnected-(JP2-Pad7)") (class "Default")
      (node (ref "JP2") (pin "7") (pinfunction "7_7") (pintype "passive"))
    )
    (net (code "87") (name "unconnected-(JP2-Pad9)") (class "Default")
      (node (ref "JP2") (pin "9") (pinfunction "9_9") (pintype "passive"))
    )
    (net (code "88") (name "unconnected-(JP2-Pad11)") (class "Default")
      (node (ref "JP2") (pin "11") (pinfunction "11_11") (pintype "passive"))
    )
    (net (code "89") (name "unconnected-(JP2-Pad13)") (class "Default")
      (node (ref "JP2") (pin "13") (pinfunction "13_13") (pintype "passive"))
    )
    (net (code "90") (name "unconnected-(JP2-Pad17)") (class "Default")
      (node (ref "JP2") (pin "17") (pinfunction "17_17") (pintype "passive"))
    )
    (net (code "91") (name "unconnected-(JP2-Pad19)") (class "Default")
      (node (ref "JP2") (pin "19") (pinfunction "19_19") (pintype "passive"))
    )
    (net (code "92") (name "unconnected-(JP2-Pad21)") (class "Default")
      (node (ref "JP2") (pin "21") (pinfunction "21_21") (pintype "passive"))
    )
    (net (code "93") (name "unconnected-(JP2-Pad25)") (class "Default")
      (node (ref "JP2") (pin "25") (pinfunction "25_25") (pintype "passive"))
    )
    (net (code "94") (name "unconnected-(JP2-Pad27)") (class "Default")
      (node (ref "JP2") (pin "27") (pinfunction "27_27") (pintype "passive"))
    )
    (net (code "95") (name "unconnected-(JP2-Pad29)") (class "Default")
      (node (ref "JP2") (pin "29") (pinfunction "29_29") (pintype "passive"))
    )
    (net (code "96") (name "unconnected-(JP2-Pad33)") (class "Default")
      (node (ref "JP2") (pin "33") (pinfunction "33_33") (pintype "passive"))
    )
    (net (code "97") (name "unconnected-(JP4-Pad1)") (class "Default")
      (node (ref "JP4") (pin "1") (pinfunction "1_1") (pintype "passive"))
    )
    (net (code "98") (name "unconnected-(JP4-Pad6)") (class "Default")
      (node (ref "JP4") (pin "6") (pinfunction "6_6") (pintype "passive"))
    )
    (net (code "99") (name "unconnected-(U$1-+3V3.1-Pad3V3.1)") (class "Default")
      (node (ref "U$1") (pin "3V3.1") (pinfunction "+3V3.1_3V3.1") (pintype "bidirectional"))
    )
    (net (code "100") (name "unconnected-(U$1-+3V3.2-Pad3V3.2)") (class "Default")
      (node (ref "U$1") (pin "3V3.2") (pinfunction "+3V3.2_3V3.2") (pintype "bidirectional"))
    )
    (net (code "101") (name "unconnected-(U$1-AREF-PadAREF.1)") (class "Default")
      (node (ref "U$1") (pin "AREF.1") (pinfunction "AREF_AREF.1") (pintype "bidirectional"))
    )
    (net (code "102") (name "unconnected-(U$1-PadA0)") (class "Default")
      (node (ref "U$1") (pin "A0") (pinfunction "A0_A0") (pintype "bidirectional"))
    )
    (net (code "103") (name "unconnected-(U$1-PadA1)") (class "Default")
      (node (ref "U$1") (pin "A1") (pinfunction "A1_A1") (pintype "bidirectional"))
    )
    (net (code "104") (name "unconnected-(U$1-PadA2)") (class "Default")
      (node (ref "U$1") (pin "A2") (pinfunction "A2_A2") (pintype "bidirectional"))
    )
    (net (code "105") (name "unconnected-(U$1-PadA3)") (class "Default")
      (node (ref "U$1") (pin "A3") (pinfunction "A3_A3") (pintype "bidirectional"))
    )
    (net (code "106") (name "unconnected-(U$1-PadA4)") (class "Default")
      (node (ref "U$1") (pin "A4") (pinfunction "A4_A4") (pintype "bidirectional"))
    )
    (net (code "107") (name "unconnected-(U$1-PadA5)") (class "Default")
      (node (ref "U$1") (pin "A5") (pinfunction "A5_A5") (pintype "bidirectional"))
    )
    (net (code "108") (name "unconnected-(U$1-PadA6)") (class "Default")
      (node (ref "U$1") (pin "A6") (pinfunction "A6_A6") (pintype "bidirectional"))
    )
    (net (code "109") (name "unconnected-(U$1-PadA7)") (class "Default")
      (node (ref "U$1") (pin "A7") (pinfunction "A7_A7") (pintype "bidirectional"))
    )
    (net (code "110") (name "unconnected-(U$1-PadA8)") (class "Default")
      (node (ref "U$1") (pin "A8") (pinfunction "A8_A8") (pintype "bidirectional"))
    )
    (net (code "111") (name "unconnected-(U$1-PadA9)") (class "Default")
      (node (ref "U$1") (pin "A9") (pinfunction "A9_A9") (pintype "bidirectional"))
    )
    (net (code "112") (name "unconnected-(U$1-PadA10)") (class "Default")
      (node (ref "U$1") (pin "A10") (pinfunction "A10_A10") (pintype "bidirectional"))
    )
    (net (code "113") (name "unconnected-(U$1-PadA11)") (class "Default")
      (node (ref "U$1") (pin "A11") (pinfunction "A11_A11") (pintype "bidirectional"))
    )
    (net (code "114") (name "unconnected-(U$1-PadA12)") (class "Default")
      (node (ref "U$1") (pin "A12") (pinfunction "A12_A12") (pintype "bidirectional"))
    )
    (net (code "115") (name "unconnected-(U$1-PadA13)") (class "Default")
      (node (ref "U$1") (pin "A13") (pinfunction "A13_A13") (pintype "bidirectional"))
    )
    (net (code "116") (name "unconnected-(U$1-PadD13)") (class "Default")
      (node (ref "U$1") (pin "D13") (pinfunction "D13_D13") (pintype "bidirectional"))
    )
    (net (code "117") (name "unconnected-(U$1-PadD18)") (class "Default")
      (node (ref "U$1") (pin "D18") (pinfunction "D18_D18") (pintype "bidirectional"))
    )
    (net (code "118") (name "unconnected-(U$1-PadD19)") (class "Default")
      (node (ref "U$1") (pin "D19") (pinfunction "D19_D19") (pintype "bidirectional"))
    )
    (net (code "119") (name "unconnected-(U$1-PadRST)") (class "Default")
      (node (ref "U$1") (pin "RST") (pinfunction "RST_RST") (pintype "bidirectional"))
    )
    (net (code "120") (name "unconnected-(U$1-PadRX)") (class "Default")
      (node (ref "U$1") (pin "RX") (pinfunction "RX_RX") (pintype "bidirectional"))
    )
    (net (code "121") (name "unconnected-(U$1-PadTX)") (class "Default")
      (node (ref "U$1") (pin "TX") (pinfunction "TX_TX") (pintype "bidirectional"))
    )
    (net (code "122") (name "unconnected-(U$1-PadVIN.1)") (class "Default")
      (node (ref "U$1") (pin "VIN.1") (pinfunction "VIN.1_VIN.1") (pintype "bidirectional"))
    )
    (net (code "123") (name "unconnected-(U$1-PadVIN.2)") (class "Default")
      (node (ref "U$1") (pin "VIN.2") (pinfunction "VIN.2_VIN.2") (pintype "bidirectional"))
    )
    (net (code "124") (name "unconnected-(U$2-P$1-Pad3V0)") (class "Default")
      (node (ref "U$2") (pin "3V0") (pinfunction "P$1_3V0") (pintype "bidirectional"))
    )
    (net (code "125") (name "unconnected-(U$2-P$2-PadADR)") (class "Default")
      (node (ref "U$2") (pin "ADR") (pinfunction "P$2_ADR") (pintype "bidirectional"))
    )
    (net (code "126") (name "unconnected-(U$2-P$4-PadINT)") (class "Default")
      (node (ref "U$2") (pin "INT") (pinfunction "P$4_INT") (pintype "bidirectional"))
    )
    (net (code "127") (name "unconnected-(U$2-P$5-PadPS0)") (class "Default")
      (node (ref "U$2") (pin "PS0") (pinfunction "P$5_PS0") (pintype "bidirectional"))
    )
    (net (code "128") (name "unconnected-(U$2-P$6-PadPS1)") (class "Default")
      (node (ref "U$2") (pin "PS1") (pinfunction "P$6_PS1") (pintype "bidirectional"))
    )
    (net (code "129") (name "unconnected-(U$2-P$7-PadRST)") (class "Default")
      (node (ref "U$2") (pin "RST") (pinfunction "P$7_RST") (pintype "bidirectional"))
    )
  )
)
